# main.net
KiCad netlist of a schematic drawn in EAGLE
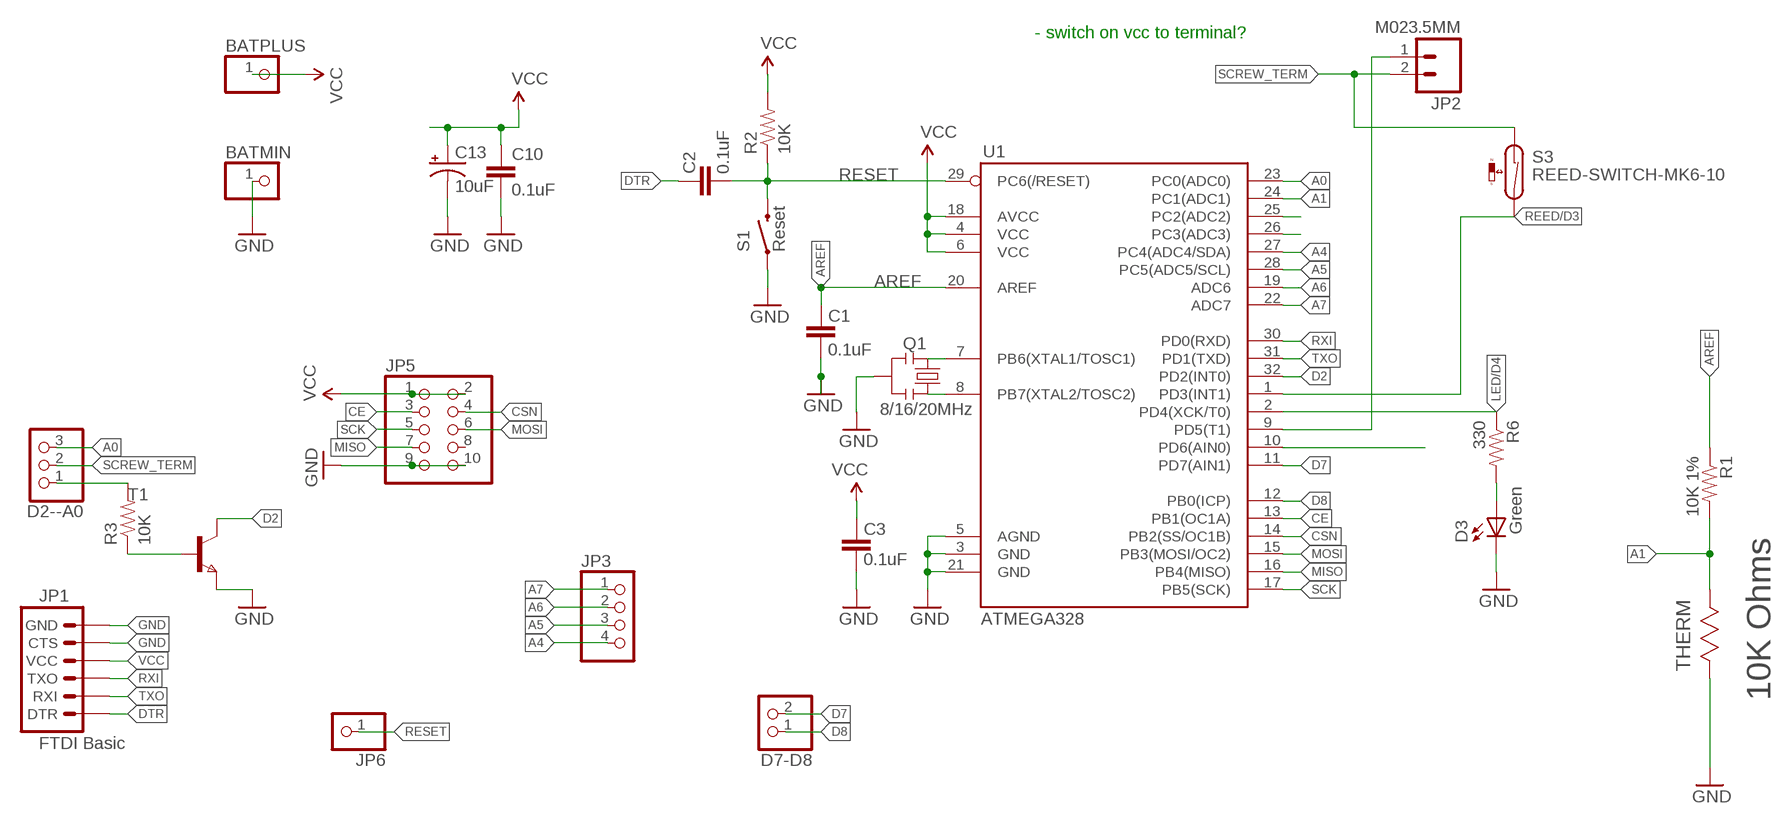
[diagram p0: schematic, sheet 1]

(export (version "E")
  (design (tool "Eeschema 10.0.6"))
  (components
    (comp (ref "BATMIN")
      (value "PINHD-1X1")
      (footprint "eagle-import:1X01")
      (libsource (lib "eagle-import") (part "PINHD-1X1"))
    )
    (comp (ref "BATPLUS")
      (value "PINHD-1X1")
      (footprint "eagle-import:1X01")
      (libsource (lib "eagle-import") (part "PINHD-1X1"))
    )
    (comp (ref "C1")
      (value "0.1uF")
      (footprint "eagle-import:0603-CAP")
      (libsource (lib "eagle-import") (part "CAP0603-CAP"))
    )
    (comp (ref "C2")
      (value "0.1uF")
      (footprint "eagle-import:0603-CAP")
      (libsource (lib "eagle-import") (part "CAP0603-CAP"))
    )
    (comp (ref "C3")
      (value "0.1uF")
      (footprint "eagle-import:0603-CAP")
      (libsource (lib "eagle-import") (part "CAP0603-CAP"))
    )
    (comp (ref "C10")
      (value "0.1uF")
      (footprint "eagle-import:0603-CAP")
      (libsource (lib "eagle-import") (part "CAP0603-CAP"))
    )
    (comp (ref "C13")
      (value "10uF")
      (footprint "eagle-import:EIA3216")
      (libsource (lib "eagle-import") (part "CAP_POL1206"))
    )
    (comp (ref "D2--A0")
      (value "PINHD-1X3")
      (footprint "eagle-import:1X03")
      (libsource (lib "eagle-import") (part "PINHD-1X3"))
    )
    (comp (ref "D3")
      (value "Green")
      (footprint "eagle-import:0603-LED-ALT1")
      (libsource (lib "eagle-import") (part "LED"))
    )
    (comp (ref "D7-D8")
      (value "PINHD-1X2")
      (footprint "eagle-import:1X02")
      (libsource (lib "eagle-import") (part "PINHD-1X2"))
    )
    (comp (ref "JP1")
      (value "FTDI Basic")
      (footprint "eagle-import:1X06")
      (libsource (lib "eagle-import") (part "ARDUINO_SERIAL_PROGRAMPTH"))
    )
    (comp (ref "JP2")
      (value "M023.5MM")
      (footprint "eagle-import:SCREWTERMINAL-3.5MM-2")
      (libsource (lib "eagle-import") (part "M023.5MM"))
    )
    (comp (ref "JP3")
      (value "PINHD-1X4")
      (footprint "eagle-import:1X04")
      (libsource (lib "eagle-import") (part "PINHD-1X4"))
    )
    (comp (ref "JP5")
      (value "PINHD-2X5")
      (footprint "eagle-import:2X05")
      (libsource (lib "eagle-import") (part "PINHD-2X5"))
    )
    (comp (ref "JP6")
      (value "PINHD-1X1")
      (footprint "eagle-import:1X01")
      (libsource (lib "eagle-import") (part "PINHD-1X1"))
    )
    (comp (ref "Q1")
      (value "8/16/20MHz")
      (footprint "eagle-import:RESONATOR-SMD-1_1")
      (libsource (lib "eagle-import") (part "RESONATOR1{colon}1"))
    )
    (comp (ref "R1")
      (value "10K 1%")
      (footprint "eagle-import:0603-RES")
      (libsource (lib "eagle-import") (part "RESISTOR0603-RES"))
    )
    (comp (ref "R2")
      (value "10K")
      (footprint "eagle-import:0603-RES")
      (libsource (lib "eagle-import") (part "RESISTOR0603-RES"))
    )
    (comp (ref "R3")
      (value "10K")
      (footprint "eagle-import:0603-RES")
      (libsource (lib "eagle-import") (part "RESISTOR0603-RES"))
    )
    (comp (ref "R6")
      (value "330")
      (footprint "eagle-import:0603-RES")
      (libsource (lib "eagle-import") (part "RESISTOR0603-RES"))
    )
    (comp (ref "S1")
      (value "Reset")
      (footprint "eagle-import:TACTILE-SWITCH-SMD-ALT01")
      (libsource (lib "eagle-import") (part "SWITCH-MOMENTARY-2SMD-ALT01"))
    )
    (comp (ref "S3")
      (value "REED-SWITCH-MK6-10")
      (footprint "eagle-import:MK6-10")
      (libsource (lib "eagle-import") (part "REED-SWITCH-MK6-10"))
    )
    (comp (ref "T1")
      (value "NPNSOT323")
      (footprint "eagle-import:SOT323")
      (fields (field (name "MPN") "DSS4160U-7"))
      (libsource (lib "eagle-import") (part "NPNSOT323"))
    )
    (comp (ref "THERM")
      (value "10K Ohms")
      (footprint "eagle-import:RESC1608X95N")
      (fields (field (name "MPN") "NTCS0603E3103HMT") (field (name "TOLERANCE") "± 3%"))
      (libsource (lib "eagle-import") (part "NTCS0603E3103HMT"))
    )
    (comp (ref "U1")
      (value "ATMEGA328")
      (footprint "eagle-import:TQFP32-08")
      (libsource (lib "eagle-import") (part "ATMEGA168"))
    )
  )
  (nets
    (net (code "1") (name "A0") (class "Default")
      (node (ref "D2--A0") (pin "3") (pinfunction "3_3") (pintype "passive"))
      (node (ref "U1") (pin "23") (pinfunction "PC0(ADC0)_23") (pintype "bidirectional"))
    )
    (net (code "2") (name "A1") (class "Default")
      (node (ref "R1") (pin "2") (pinfunction "2_2") (pintype "passive"))
      (node (ref "THERM") (pin "1") (pinfunction "1_1") (pintype "passive"))
      (node (ref "U1") (pin "24") (pinfunction "PC1(ADC1)_24") (pintype "bidirectional"))
    )
    (net (code "3") (name "A4") (class "Default")
      (node (ref "JP3") (pin "4") (pinfunction "4_4") (pintype "passive"))
      (node (ref "U1") (pin "27") (pinfunction "PC4(ADC4/SDA)_27") (pintype "bidirectional"))
    )
    (net (code "4") (name "A5") (class "Default")
      (node (ref "JP3") (pin "3") (pinfunction "3_3") (pintype "passive"))
      (node (ref "U1") (pin "28") (pinfunction "PC5(ADC5/SCL)_28") (pintype "bidirectional"))
    )
    (net (code "5") (name "A6") (class "Default")
      (node (ref "JP3") (pin "2") (pinfunction "2_2") (pintype "passive"))
      (node (ref "U1") (pin "19") (pinfunction "ADC6_19") (pintype "bidirectional"))
    )
    (net (code "6") (name "A7") (class "Default")
      (node (ref "JP3") (pin "1") (pinfunction "1_1") (pintype "passive"))
      (node (ref "U1") (pin "22") (pinfunction "ADC7_22") (pintype "bidirectional"))
    )
    (net (code "7") (name "AREF") (class "Default")
      (node (ref "C1") (pin "2") (pinfunction "2_2") (pintype "passive"))
      (node (ref "R1") (pin "1") (pinfunction "1_1") (pintype "passive"))
      (node (ref "U1") (pin "20") (pinfunction "AREF_20") (pintype "bidirectional"))
    )
    (net (code "8") (name "CE") (class "Default")
      (node (ref "JP5") (pin "3") (pinfunction "3_3") (pintype "passive"))
      (node (ref "U1") (pin "13") (pinfunction "PB1(OC1A)_13") (pintype "bidirectional"))
    )
    (net (code "9") (name "CSN") (class "Default")
      (node (ref "JP5") (pin "4") (pinfunction "4_4") (pintype "passive"))
      (node (ref "U1") (pin "14") (pinfunction "PB2(SS/OC1B)_14") (pintype "bidirectional"))
    )
    (net (code "10") (name "D2") (class "Default")
      (node (ref "T1") (pin "1") (pinfunction "C_1") (pintype "passive"))
      (node (ref "U1") (pin "32") (pinfunction "PD2(INT0)_32") (pintype "bidirectional"))
    )
    (net (code "11") (name "D7") (class "Default")
      (node (ref "D7-D8") (pin "2") (pinfunction "2_2") (pintype "passive"))
      (node (ref "U1") (pin "11") (pinfunction "PD7(AIN1)_11") (pintype "bidirectional"))
    )
    (net (code "12") (name "D8") (class "Default")
      (node (ref "D7-D8") (pin "1") (pinfunction "1_1") (pintype "passive"))
      (node (ref "U1") (pin "12") (pinfunction "PB0(ICP)_12") (pintype "bidirectional"))
    )
    (net (code "13") (name "DTR") (class "Default")
      (node (ref "C2") (pin "2") (pinfunction "2_2") (pintype "passive"))
      (node (ref "JP1") (pin "1") (pinfunction "DTR_1") (pintype "passive"))
    )
    (net (code "14") (name "GND") (class "Default")
      (node (ref "BATMIN") (pin "1") (pinfunction "1_1") (pintype "passive"))
      (node (ref "C1") (pin "1") (pinfunction "1_1") (pintype "passive"))
      (node (ref "C10") (pin "2") (pinfunction "2_2") (pintype "passive"))
      (node (ref "C13") (pin "C") (pinfunction "-_C") (pintype "passive"))
      (node (ref "C3") (pin "1") (pinfunction "1_1") (pintype "passive"))
      (node (ref "D3") (pin "C") (pinfunction "C_C") (pintype "passive"))
      (node (ref "JP1") (pin "5") (pinfunction "CTS_5") (pintype "passive"))
      (node (ref "JP1") (pin "6") (pinfunction "GND_6") (pintype "passive"))
      (node (ref "JP5") (pin "10") (pinfunction "10_10") (pintype "passive"))
      (node (ref "JP5") (pin "9") (pinfunction "9_9") (pintype "passive"))
      (node (ref "Q1") (pin "2") (pinfunction "2_2") (pintype "passive"))
      (node (ref "S1") (pin "1") (pinfunction "1_1") (pintype "passive"))
      (node (ref "S1") (pin "2") (pinfunction "1_2") (pintype "passive"))
      (node (ref "T1") (pin "3") (pinfunction "E_3") (pintype "passive"))
      (node (ref "THERM") (pin "2") (pinfunction "2_2") (pintype "passive"))
      (node (ref "U1") (pin "21") (pinfunction "GND_21") (pintype "bidirectional"))
      (node (ref "U1") (pin "3") (pinfunction "GND_3") (pintype "bidirectional"))
      (node (ref "U1") (pin "5") (pinfunction "AGND_5") (pintype "bidirectional"))
    )
    (net (code "15") (name "LED{slash}D4") (class "Default")
      (node (ref "R6") (pin "1") (pinfunction "1_1") (pintype "passive"))
      (node (ref "U1") (pin "2") (pinfunction "PD4(XCK/T0)_2") (pintype "bidirectional"))
    )
    (net (code "16") (name "MISO") (class "Default")
      (node (ref "JP5") (pin "7") (pinfunction "7_7") (pintype "passive"))
      (node (ref "U1") (pin "16") (pinfunction "PB4(MISO)_16") (pintype "bidirectional"))
    )
    (net (code "17") (name "MOSI") (class "Default")
      (node (ref "JP5") (pin "6") (pinfunction "6_6") (pintype "passive"))
      (node (ref "U1") (pin "15") (pinfunction "PB3(MOSI/OC2)_15") (pintype "bidirectional"))
    )
    (net (code "18") (name "Net-(D2--A0-Pad1)") (class "Default")
      (node (ref "D2--A0") (pin "1") (pinfunction "1_1") (pintype "passive"))
      (node (ref "R3") (pin "2") (pinfunction "2_2") (pintype "passive"))
    )
    (net (code "19") (name "Net-(D3-PadA)") (class "Default")
      (node (ref "D3") (pin "A") (pinfunction "A_A") (pintype "passive"))
      (node (ref "R6") (pin "2") (pinfunction "2_2") (pintype "passive"))
    )
    (net (code "20") (name "Net-(T1-B)") (class "Default")
      (node (ref "R3") (pin "1") (pinfunction "1_1") (pintype "passive"))
      (node (ref "T1") (pin "2") (pinfunction "B_2") (pintype "passive"))
    )
    (net (code "21") (name "Net-(U1-PB6(XTAL1{slash}TOSC1))") (class "Default")
      (node (ref "Q1") (pin "1") (pinfunction "1_1") (pintype "passive"))
      (node (ref "U1") (pin "7") (pinfunction "PB6(XTAL1/TOSC1)_7") (pintype "bidirectional"))
    )
    (net (code "22") (name "Net-(U1-PB7(XTAL2{slash}TOSC2))") (class "Default")
      (node (ref "Q1") (pin "3") (pinfunction "3_3") (pintype "passive"))
      (node (ref "U1") (pin "8") (pinfunction "PB7(XTAL2/TOSC2)_8") (pintype "bidirectional"))
    )
    (net (code "23") (name "Net-(U1-PD5(T1))") (class "Default")
      (node (ref "JP2") (pin "1") (pinfunction "1_1") (pintype "passive"))
      (node (ref "U1") (pin "9") (pinfunction "PD5(T1)_9") (pintype "bidirectional"))
    )
    (net (code "24") (name "REED{slash}D3") (class "Default")
      (node (ref "S3") (pin "2") (pinfunction "2_2") (pintype "passive"))
      (node (ref "U1") (pin "1") (pinfunction "PD3(INT1)_1") (pintype "bidirectional"))
    )
    (net (code "25") (name "RESET") (class "Default")
      (node (ref "C2") (pin "1") (pinfunction "1_1") (pintype "passive"))
      (node (ref "JP6") (pin "1") (pinfunction "1_1") (pintype "passive"))
      (node (ref "R2") (pin "1") (pinfunction "1_1") (pintype "passive"))
      (node (ref "S1") (pin "3") (pinfunction "2_3") (pintype "passive"))
      (node (ref "S1") (pin "4") (pinfunction "2_4") (pintype "passive"))
      (node (ref "U1") (pin "29") (pinfunction "PC6(/RESET)_29") (pintype "bidirectional"))
    )
    (net (code "26") (name "RXI") (class "Default")
      (node (ref "JP1") (pin "3") (pinfunction "TXO_3") (pintype "passive"))
      (node (ref "U1") (pin "30") (pinfunction "PD0(RXD)_30") (pintype "bidirectional"))
    )
    (net (code "27") (name "SCK") (class "Default")
      (node (ref "JP5") (pin "5") (pinfunction "5_5") (pintype "passive"))
      (node (ref "U1") (pin "17") (pinfunction "PB5(SCK)_17") (pintype "bidirectional"))
    )
    (net (code "28") (name "SCREW_TERM") (class "Default")
      (node (ref "D2--A0") (pin "2") (pinfunction "2_2") (pintype "passive"))
      (node (ref "JP2") (pin "2") (pinfunction "2_2") (pintype "passive"))
      (node (ref "S3") (pin "1") (pinfunction "1_1") (pintype "passive"))
    )
    (net (code "29") (name "TXO") (class "Default")
      (node (ref "JP1") (pin "2") (pinfunction "RXI_2") (pintype "passive"))
      (node (ref "U1") (pin "31") (pinfunction "PD1(TXD)_31") (pintype "bidirectional"))
    )
    (net (code "30") (name "VCC") (class "Default")
      (node (ref "BATPLUS") (pin "1") (pinfunction "1_1") (pintype "passive"))
      (node (ref "C10") (pin "1") (pinfunction "1_1") (pintype "passive"))
      (node (ref "C13") (pin "A") (pinfunction "+_A") (pintype "passive"))
      (node (ref "C3") (pin "2") (pinfunction "2_2") (pintype "passive"))
      (node (ref "JP1") (pin "4") (pinfunction "VCC_4") (pintype "passive"))
      (node (ref "JP5") (pin "1") (pinfunction "1_1") (pintype "passive"))
      (node (ref "JP5") (pin "2") (pinfunction "2_2") (pintype "passive"))
      (node (ref "R2") (pin "2") (pinfunction "2_2") (pintype "passive"))
      (node (ref "U1") (pin "18") (pinfunction "AVCC_18") (pintype "bidirectional"))
      (node (ref "U1") (pin "4") (pinfunction "VCC_4") (pintype "bidirectional"))
      (node (ref "U1") (pin "6") (pinfunction "VCC_6") (pintype "bidirectional"))
    )
    (net (code "31") (name "unconnected-(JP5-Pad8)") (class "Default")
      (node (ref "JP5") (pin "8") (pinfunction "8_8") (pintype "passive"))
    )
    (net (code "32") (name "unconnected-(U1-PC2(ADC2)-Pad25)") (class "Default")
      (node (ref "U1") (pin "25") (pinfunction "PC2(ADC2)_25") (pintype "bidirectional"))
    )
    (net (code "33") (name "unconnected-(U1-PC3(ADC3)-Pad26)") (class "Default")
      (node (ref "U1") (pin "26") (pinfunction "PC3(ADC3)_26") (pintype "bidirectional"))
    )
    (net (code "34") (name "unconnected-(U1-PD6(AIN0)-Pad10)") (class "Default")
      (node (ref "U1") (pin "10") (pinfunction "PD6(AIN0)_10") (pintype "bidirectional"))
    )
  )
)
